# veter-cap.net
KiCad netlist of a schematic drawn in EAGLE
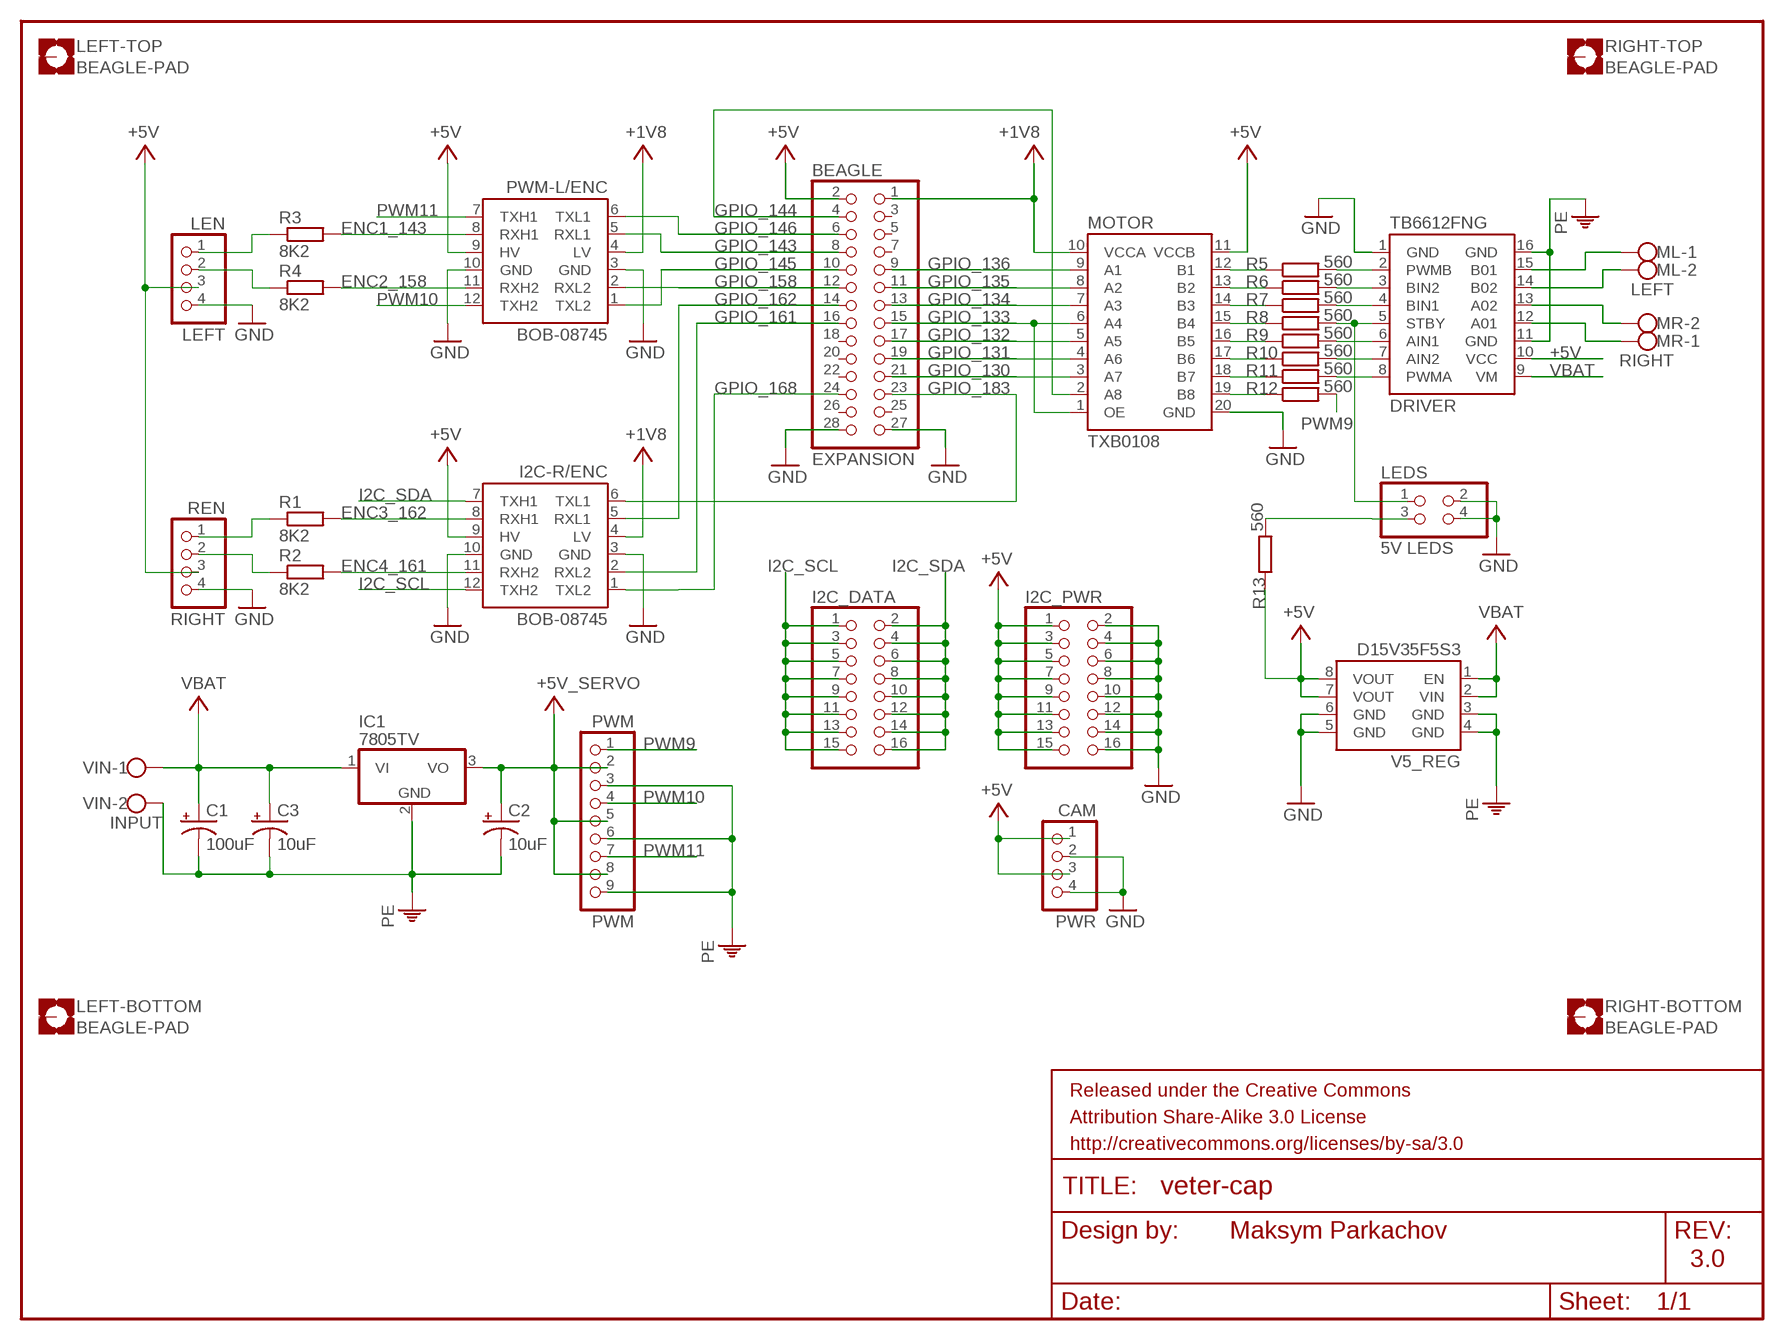
[diagram p0: schematic, sheet 1]

(export (version "E")
  (design (tool "Eeschema 10.0.6"))
  (components
    (comp (ref "BEAGLE")
      (value "EXPANSION")
      (footprint "eagle-import:BEAGLE_PINH2X14")
      (libsource (lib "eagle-import") (part "BEAGLE_EXPANSION"))
    )
    (comp (ref "C1")
      (value "100uF")
      (footprint "eagle-import:CPOL-RADIAL-10UF-25V")
      (libsource (lib "eagle-import") (part "CAP_POLPTH2"))
    )
    (comp (ref "C2")
      (value "10uF")
      (footprint "eagle-import:CPOL-RADIAL-10UF-25V")
      (libsource (lib "eagle-import") (part "CAP_POLPTH2"))
    )
    (comp (ref "C3")
      (value "10uF")
      (footprint "eagle-import:CPOL-RADIAL-10UF-25V")
      (libsource (lib "eagle-import") (part "CAP_POLPTH2"))
    )
    (comp (ref "CAM")
      (value "PWR")
      (footprint "eagle-import:1X04_90")
      (libsource (lib "eagle-import") (part "PINHD-1X4/90"))
    )
    (comp (ref "DRIVER")
      (value "TB6612FNG")
      (footprint "eagle-import:6612-BREAKOUT")
      (libsource (lib "eagle-import") (part "TB6612FNG"))
    )
    (comp (ref "FRAME1")
      (value "FRAME-LETTER")
      (footprint "eagle-import:CREATIVE_COMMONS")
      (libsource (lib "eagle-import") (part "FRAME-LETTER"))
    )
    (comp (ref "I2C-R/ENC")
      (value "BOB-08745")
      (footprint "eagle-import:BOB-08745-BREAKOUT")
      (libsource (lib "eagle-import") (part "BOB-08745"))
    )
    (comp (ref "I2C_DATA")
      (value "PINHD-2X8")
      (footprint "eagle-import:2X08")
      (libsource (lib "eagle-import") (part "PINHD-2X8"))
    )
    (comp (ref "I2C_PWR")
      (value "PINHD-2X8")
      (footprint "eagle-import:2X08")
      (libsource (lib "eagle-import") (part "PINHD-2X8"))
    )
    (comp (ref "IC1")
      (value "7805TV")
      (footprint "eagle-import:TO220V")
      (libsource (lib "eagle-import") (part "78TV05"))
    )
    (comp (ref "LEDS")
      (value "5V LEDS")
      (footprint "eagle-import:2X02")
      (libsource (lib "eagle-import") (part "PINHD-2X2"))
    )
    (comp (ref "LEFT-BOTTOM")
      (value "BEAGLE-PAD")
      (footprint "eagle-import:BEAGLE-PAD")
      (libsource (lib "eagle-import") (part "BEAGLE-PAD"))
    )
    (comp (ref "LEFT-TOP")
      (value "BEAGLE-PAD")
      (footprint "eagle-import:BEAGLE-PAD")
      (libsource (lib "eagle-import") (part "BEAGLE-PAD"))
    )
    (comp (ref "LEN")
      (value "LEFT")
      (footprint "eagle-import:1X04_90")
      (libsource (lib "eagle-import") (part "PINHD-1X4/90"))
    )
    (comp (ref "ML")
      (value "LEFT")
      (footprint "eagle-import:W237-102")
      (fields (field (name "MPN") "237-102"))
      (libsource (lib "eagle-import") (part "W237-102"))
    )
    (comp (ref "MOTOR")
      (value "TXB0108")
      (footprint "eagle-import:TXB0108-BREAKOUT")
      (libsource (lib "eagle-import") (part "TXB0108"))
    )
    (comp (ref "MR")
      (value "RIGHT")
      (footprint "eagle-import:W237-102")
      (fields (field (name "MPN") "237-102"))
      (libsource (lib "eagle-import") (part "W237-102"))
    )
    (comp (ref "PWM")
      (value "PWM")
      (footprint "eagle-import:1X09_90")
      (libsource (lib "eagle-import") (part "PINHD-1X9/90"))
    )
    (comp (ref "PWM-L/ENC")
      (value "BOB-08745")
      (footprint "eagle-import:BOB-08745-BREAKOUT")
      (libsource (lib "eagle-import") (part "BOB-08745"))
    )
    (comp (ref "R1")
      (value "8K2")
      (footprint "eagle-import:0207_10")
      (libsource (lib "eagle-import") (part "R-EU_0207/10"))
    )
    (comp (ref "R2")
      (value "8K2")
      (footprint "eagle-import:0207_10")
      (libsource (lib "eagle-import") (part "R-EU_0207/10"))
    )
    (comp (ref "R3")
      (value "8K2")
      (footprint "eagle-import:0207_10")
      (libsource (lib "eagle-import") (part "R-EU_0207/10"))
    )
    (comp (ref "R4")
      (value "8K2")
      (footprint "eagle-import:0207_10")
      (libsource (lib "eagle-import") (part "R-EU_0207/10"))
    )
    (comp (ref "R5")
      (value "560")
      (footprint "eagle-import:0207_10")
      (libsource (lib "eagle-import") (part "R-EU_0207/10"))
    )
    (comp (ref "R6")
      (value "560")
      (footprint "eagle-import:0207_10")
      (libsource (lib "eagle-import") (part "R-EU_0207/10"))
    )
    (comp (ref "R7")
      (value "560")
      (footprint "eagle-import:0207_10")
      (libsource (lib "eagle-import") (part "R-EU_0207/10"))
    )
    (comp (ref "R8")
      (value "560")
      (footprint "eagle-import:0207_10")
      (libsource (lib "eagle-import") (part "R-EU_0207/10"))
    )
    (comp (ref "R9")
      (value "560")
      (footprint "eagle-import:0207_10")
      (libsource (lib "eagle-import") (part "R-EU_0207/10"))
    )
    (comp (ref "R10")
      (value "560")
      (footprint "eagle-import:0207_10")
      (libsource (lib "eagle-import") (part "R-EU_0207/10"))
    )
    (comp (ref "R11")
      (value "560")
      (footprint "eagle-import:0207_10")
      (libsource (lib "eagle-import") (part "R-EU_0207/10"))
    )
    (comp (ref "R12")
      (value "560")
      (footprint "eagle-import:0207_10")
      (libsource (lib "eagle-import") (part "R-EU_0207/10"))
    )
    (comp (ref "R13")
      (value "560")
      (footprint "eagle-import:0207_10")
      (libsource (lib "eagle-import") (part "R-EU_0207/10"))
    )
    (comp (ref "REN")
      (value "RIGHT")
      (footprint "eagle-import:1X04_90")
      (libsource (lib "eagle-import") (part "PINHD-1X4/90"))
    )
    (comp (ref "RIGHT-BOTTOM")
      (value "BEAGLE-PAD")
      (footprint "eagle-import:BEAGLE-PAD")
      (libsource (lib "eagle-import") (part "BEAGLE-PAD"))
    )
    (comp (ref "RIGHT-TOP")
      (value "BEAGLE-PAD")
      (footprint "eagle-import:BEAGLE-PAD")
      (libsource (lib "eagle-import") (part "BEAGLE-PAD"))
    )
    (comp (ref "V5_REG")
      (value "D15V35F5S3")
      (footprint "eagle-import:D15V35F5S3-BREAKOUT")
      (libsource (lib "eagle-import") (part "D15V35F5S3"))
    )
    (comp (ref "VIN")
      (value "INPUT")
      (footprint "eagle-import:W237-102")
      (fields (field (name "MPN") "237-102"))
      (libsource (lib "eagle-import") (part "W237-102"))
    )
  )
  (nets
    (net (code "1") (name "+1V8") (class "Default")
      (node (ref "BEAGLE") (pin "1") (pinfunction "1_1") (pintype "passive"))
      (node (ref "I2C-R/ENC") (pin "4") (pinfunction "LV_4") (pintype "power_in"))
      (node (ref "MOTOR") (pin "10") (pinfunction "VCCA_10") (pintype "power_in"))
      (node (ref "PWM-L/ENC") (pin "4") (pinfunction "LV_4") (pintype "power_in"))
    )
    (net (code "2") (name "+5V") (class "Default")
      (node (ref "BEAGLE") (pin "2") (pinfunction "2_2") (pintype "passive"))
      (node (ref "CAM") (pin "1") (pinfunction "1_1") (pintype "passive"))
      (node (ref "CAM") (pin "3") (pinfunction "3_3") (pintype "passive"))
      (node (ref "DRIVER") (pin "10") (pinfunction "VCC_10") (pintype "power_in"))
      (node (ref "I2C-R/ENC") (pin "9") (pinfunction "HV_9") (pintype "power_in"))
      (node (ref "I2C_PWR") (pin "1") (pinfunction "1_1") (pintype "passive"))
      (node (ref "I2C_PWR") (pin "11") (pinfunction "11_11") (pintype "passive"))
      (node (ref "I2C_PWR") (pin "13") (pinfunction "13_13") (pintype "passive"))
      (node (ref "I2C_PWR") (pin "15") (pinfunction "15_15") (pintype "passive"))
      (node (ref "I2C_PWR") (pin "3") (pinfunction "3_3") (pintype "passive"))
      (node (ref "I2C_PWR") (pin "5") (pinfunction "5_5") (pintype "passive"))
      (node (ref "I2C_PWR") (pin "7") (pinfunction "7_7") (pintype "passive"))
      (node (ref "I2C_PWR") (pin "9") (pinfunction "9_9") (pintype "passive"))
      (node (ref "LEN") (pin "3") (pinfunction "3_3") (pintype "passive"))
      (node (ref "MOTOR") (pin "11") (pinfunction "VCCB_11") (pintype "power_in"))
      (node (ref "PWM-L/ENC") (pin "9") (pinfunction "HV_9") (pintype "power_in"))
      (node (ref "R13") (pin "1") (pinfunction "1_1") (pintype "passive"))
      (node (ref "REN") (pin "3") (pinfunction "3_3") (pintype "passive"))
      (node (ref "V5_REG") (pin "7") (pinfunction "VOUT_7") (pintype "power_in"))
      (node (ref "V5_REG") (pin "8") (pinfunction "VOUT_8") (pintype "power_in"))
    )
    (net (code "3") (name "+5V_SERVO") (class "Default")
      (node (ref "C2") (pin "1") (pinfunction "+_1") (pintype "passive"))
      (node (ref "IC1") (pin "3") (pinfunction "VO_3") (pintype "passive"))
      (node (ref "PWM") (pin "2") (pinfunction "2_2") (pintype "passive"))
      (node (ref "PWM") (pin "5") (pinfunction "5_5") (pintype "passive"))
      (node (ref "PWM") (pin "8") (pinfunction "8_8") (pintype "passive"))
    )
    (net (code "4") (name "/ENC1_143") (class "Default")
      (node (ref "PWM-L/ENC") (pin "8") (pinfunction "RXH1_8") (pintype "input"))
      (node (ref "R3") (pin "2") (pinfunction "2_2") (pintype "passive"))
    )
    (net (code "5") (name "/ENC2_158") (class "Default")
      (node (ref "PWM-L/ENC") (pin "11") (pinfunction "RXH2_11") (pintype "input"))
      (node (ref "R4") (pin "2") (pinfunction "2_2") (pintype "passive"))
    )
    (net (code "6") (name "/ENC3_162") (class "Default")
      (node (ref "I2C-R/ENC") (pin "8") (pinfunction "RXH1_8") (pintype "input"))
      (node (ref "R1") (pin "2") (pinfunction "2_2") (pintype "passive"))
    )
    (net (code "7") (name "/ENC4_161") (class "Default")
      (node (ref "I2C-R/ENC") (pin "11") (pinfunction "RXH2_11") (pintype "input"))
      (node (ref "R2") (pin "2") (pinfunction "2_2") (pintype "passive"))
    )
    (net (code "8") (name "/GPIO_130") (class "Default")
      (node (ref "BEAGLE") (pin "21") (pinfunction "21_21") (pintype "passive"))
      (node (ref "MOTOR") (pin "3") (pinfunction "A7_3") (pintype "input"))
    )
    (net (code "9") (name "/GPIO_131") (class "Default")
      (node (ref "BEAGLE") (pin "19") (pinfunction "19_19") (pintype "passive"))
      (node (ref "MOTOR") (pin "4") (pinfunction "A6_4") (pintype "input"))
    )
    (net (code "10") (name "/GPIO_132") (class "Default")
      (node (ref "BEAGLE") (pin "17") (pinfunction "17_17") (pintype "passive"))
      (node (ref "MOTOR") (pin "5") (pinfunction "A5_5") (pintype "input"))
    )
    (net (code "11") (name "/GPIO_133") (class "Default")
      (node (ref "BEAGLE") (pin "15") (pinfunction "15_15") (pintype "passive"))
      (node (ref "MOTOR") (pin "1") (pinfunction "OE_1") (pintype "input"))
      (node (ref "MOTOR") (pin "6") (pinfunction "A4_6") (pintype "input"))
    )
    (net (code "12") (name "/GPIO_134") (class "Default")
      (node (ref "BEAGLE") (pin "13") (pinfunction "13_13") (pintype "passive"))
      (node (ref "MOTOR") (pin "7") (pinfunction "A3_7") (pintype "input"))
    )
    (net (code "13") (name "/GPIO_135") (class "Default")
      (node (ref "BEAGLE") (pin "11") (pinfunction "11_11") (pintype "passive"))
      (node (ref "MOTOR") (pin "8") (pinfunction "A2_8") (pintype "bidirectional"))
    )
    (net (code "14") (name "/GPIO_136") (class "Default")
      (node (ref "BEAGLE") (pin "9") (pinfunction "9_9") (pintype "passive"))
      (node (ref "MOTOR") (pin "9") (pinfunction "A1_9") (pintype "input"))
    )
    (net (code "15") (name "/GPIO_143") (class "Default")
      (node (ref "BEAGLE") (pin "8") (pinfunction "8_8") (pintype "passive"))
      (node (ref "PWM-L/ENC") (pin "5") (pinfunction "RXL1_5") (pintype "output"))
    )
    (net (code "16") (name "/GPIO_144") (class "Default")
      (node (ref "BEAGLE") (pin "4") (pinfunction "4_4") (pintype "passive"))
      (node (ref "MOTOR") (pin "2") (pinfunction "A8_2") (pintype "input"))
    )
    (net (code "17") (name "/GPIO_145") (class "Default")
      (node (ref "BEAGLE") (pin "10") (pinfunction "10_10") (pintype "passive"))
      (node (ref "PWM-L/ENC") (pin "1") (pinfunction "TXL2_1") (pintype "input"))
    )
    (net (code "18") (name "/GPIO_146") (class "Default")
      (node (ref "BEAGLE") (pin "6") (pinfunction "6_6") (pintype "passive"))
      (node (ref "PWM-L/ENC") (pin "6") (pinfunction "TXL1_6") (pintype "input"))
    )
    (net (code "19") (name "/GPIO_158") (class "Default")
      (node (ref "BEAGLE") (pin "12") (pinfunction "12_12") (pintype "passive"))
      (node (ref "PWM-L/ENC") (pin "2") (pinfunction "RXL2_2") (pintype "output"))
    )
    (net (code "20") (name "/GPIO_161") (class "Default")
      (node (ref "BEAGLE") (pin "16") (pinfunction "16_16") (pintype "passive"))
      (node (ref "I2C-R/ENC") (pin "2") (pinfunction "RXL2_2") (pintype "output"))
    )
    (net (code "21") (name "/GPIO_162") (class "Default")
      (node (ref "BEAGLE") (pin "14") (pinfunction "14_14") (pintype "passive"))
      (node (ref "I2C-R/ENC") (pin "5") (pinfunction "RXL1_5") (pintype "output"))
    )
    (net (code "22") (name "/GPIO_168") (class "Default")
      (node (ref "BEAGLE") (pin "24") (pinfunction "24_24") (pintype "passive"))
      (node (ref "I2C-R/ENC") (pin "1") (pinfunction "TXL2_1") (pintype "input"))
    )
    (net (code "23") (name "/GPIO_183") (class "Default")
      (node (ref "BEAGLE") (pin "23") (pinfunction "23_23") (pintype "passive"))
      (node (ref "I2C-R/ENC") (pin "6") (pinfunction "TXL1_6") (pintype "input"))
    )
    (net (code "24") (name "/I2C_SCL") (class "Default")
      (node (ref "I2C-R/ENC") (pin "12") (pinfunction "TXH2_12") (pintype "output"))
      (node (ref "I2C_DATA") (pin "1") (pinfunction "1_1") (pintype "passive"))
      (node (ref "I2C_DATA") (pin "11") (pinfunction "11_11") (pintype "passive"))
      (node (ref "I2C_DATA") (pin "13") (pinfunction "13_13") (pintype "passive"))
      (node (ref "I2C_DATA") (pin "15") (pinfunction "15_15") (pintype "passive"))
      (node (ref "I2C_DATA") (pin "3") (pinfunction "3_3") (pintype "passive"))
      (node (ref "I2C_DATA") (pin "5") (pinfunction "5_5") (pintype "passive"))
      (node (ref "I2C_DATA") (pin "7") (pinfunction "7_7") (pintype "passive"))
      (node (ref "I2C_DATA") (pin "9") (pinfunction "9_9") (pintype "passive"))
    )
    (net (code "25") (name "/I2C_SDA") (class "Default")
      (node (ref "I2C-R/ENC") (pin "7") (pinfunction "TXH1_7") (pintype "output"))
      (node (ref "I2C_DATA") (pin "10") (pinfunction "10_10") (pintype "passive"))
      (node (ref "I2C_DATA") (pin "12") (pinfunction "12_12") (pintype "passive"))
      (node (ref "I2C_DATA") (pin "14") (pinfunction "14_14") (pintype "passive"))
      (node (ref "I2C_DATA") (pin "16") (pinfunction "16_16") (pintype "passive"))
      (node (ref "I2C_DATA") (pin "2") (pinfunction "2_2") (pintype "passive"))
      (node (ref "I2C_DATA") (pin "4") (pinfunction "4_4") (pintype "passive"))
      (node (ref "I2C_DATA") (pin "6") (pinfunction "6_6") (pintype "passive"))
      (node (ref "I2C_DATA") (pin "8") (pinfunction "8_8") (pintype "passive"))
    )
    (net (code "26") (name "/PWM9") (class "Default")
      (node (ref "PWM") (pin "1") (pinfunction "1_1") (pintype "passive"))
      (node (ref "R12") (pin "2") (pinfunction "2_2") (pintype "passive"))
    )
    (net (code "27") (name "/PWM10") (class "Default")
      (node (ref "PWM") (pin "4") (pinfunction "4_4") (pintype "passive"))
      (node (ref "PWM-L/ENC") (pin "12") (pinfunction "TXH2_12") (pintype "output"))
    )
    (net (code "28") (name "/PWM11") (class "Default")
      (node (ref "PWM") (pin "7") (pinfunction "7_7") (pintype "passive"))
      (node (ref "PWM-L/ENC") (pin "7") (pinfunction "TXH1_7") (pintype "output"))
    )
    (net (code "29") (name "GND") (class "Default")
      (node (ref "BEAGLE") (pin "27") (pinfunction "27_27") (pintype "passive"))
      (node (ref "BEAGLE") (pin "28") (pinfunction "28_28") (pintype "passive"))
      (node (ref "CAM") (pin "2") (pinfunction "2_2") (pintype "passive"))
      (node (ref "CAM") (pin "4") (pinfunction "4_4") (pintype "passive"))
      (node (ref "DRIVER") (pin "1") (pinfunction "GND_1") (pintype "power_in"))
      (node (ref "I2C-R/ENC") (pin "10") (pinfunction "GND_10") (pintype "power_in"))
      (node (ref "I2C-R/ENC") (pin "3") (pinfunction "GND_3") (pintype "power_in"))
      (node (ref "I2C_PWR") (pin "10") (pinfunction "10_10") (pintype "passive"))
      (node (ref "I2C_PWR") (pin "12") (pinfunction "12_12") (pintype "passive"))
      (node (ref "I2C_PWR") (pin "14") (pinfunction "14_14") (pintype "passive"))
      (node (ref "I2C_PWR") (pin "16") (pinfunction "16_16") (pintype "passive"))
      (node (ref "I2C_PWR") (pin "2") (pinfunction "2_2") (pintype "passive"))
      (node (ref "I2C_PWR") (pin "4") (pinfunction "4_4") (pintype "passive"))
      (node (ref "I2C_PWR") (pin "6") (pinfunction "6_6") (pintype "passive"))
      (node (ref "I2C_PWR") (pin "8") (pinfunction "8_8") (pintype "passive"))
      (node (ref "LEDS") (pin "2") (pinfunction "2_2") (pintype "passive"))
      (node (ref "LEDS") (pin "4") (pinfunction "4_4") (pintype "passive"))
      (node (ref "LEN") (pin "4") (pinfunction "4_4") (pintype "passive"))
      (node (ref "MOTOR") (pin "20") (pinfunction "GND_20") (pintype "power_in"))
      (node (ref "PWM-L/ENC") (pin "10") (pinfunction "GND_10") (pintype "power_in"))
      (node (ref "PWM-L/ENC") (pin "3") (pinfunction "GND_3") (pintype "power_in"))
      (node (ref "REN") (pin "4") (pinfunction "4_4") (pintype "passive"))
      (node (ref "V5_REG") (pin "5") (pinfunction "GND_5") (pintype "power_in"))
      (node (ref "V5_REG") (pin "6") (pinfunction "GND_6") (pintype "power_in"))
    )
    (net (code "30") (name "Net-(DRIVER-A01)") (class "Default")
      (node (ref "DRIVER") (pin "12") (pinfunction "A01_12") (pintype "output"))
      (node (ref "MR") (pin "1") (pinfunction "KL_1") (pintype "passive"))
    )
    (net (code "31") (name "Net-(DRIVER-A02)") (class "Default")
      (node (ref "DRIVER") (pin "13") (pinfunction "A02_13") (pintype "output"))
      (node (ref "MR") (pin "2") (pinfunction "KL_2") (pintype "passive"))
    )
    (net (code "32") (name "Net-(DRIVER-AIN1)") (class "Default")
      (node (ref "DRIVER") (pin "6") (pinfunction "AIN1_6") (pintype "bidirectional"))
      (node (ref "R9") (pin "2") (pinfunction "2_2") (pintype "passive"))
    )
    (net (code "33") (name "Net-(DRIVER-AIN2)") (class "Default")
      (node (ref "DRIVER") (pin "7") (pinfunction "AIN2_7") (pintype "input"))
      (node (ref "R10") (pin "2") (pinfunction "2_2") (pintype "passive"))
    )
    (net (code "34") (name "Net-(DRIVER-B01)") (class "Default")
      (node (ref "DRIVER") (pin "15") (pinfunction "B01_15") (pintype "output"))
      (node (ref "ML") (pin "1") (pinfunction "KL_1") (pintype "passive"))
    )
    (net (code "35") (name "Net-(DRIVER-B02)") (class "Default")
      (node (ref "DRIVER") (pin "14") (pinfunction "B02_14") (pintype "output"))
      (node (ref "ML") (pin "2") (pinfunction "KL_2") (pintype "passive"))
    )
    (net (code "36") (name "Net-(DRIVER-BIN1)") (class "Default")
      (node (ref "DRIVER") (pin "4") (pinfunction "BIN1_4") (pintype "input"))
      (node (ref "R7") (pin "2") (pinfunction "2_2") (pintype "passive"))
    )
    (net (code "37") (name "Net-(DRIVER-BIN2)") (class "Default")
      (node (ref "DRIVER") (pin "3") (pinfunction "BIN2_3") (pintype "input"))
      (node (ref "R6") (pin "2") (pinfunction "2_2") (pintype "passive"))
    )
    (net (code "38") (name "Net-(DRIVER-PWMA)") (class "Default")
      (node (ref "DRIVER") (pin "8") (pinfunction "PWMA_8") (pintype "input"))
      (node (ref "R11") (pin "2") (pinfunction "2_2") (pintype "passive"))
    )
    (net (code "39") (name "Net-(DRIVER-PWMB)") (class "Default")
      (node (ref "DRIVER") (pin "2") (pinfunction "PWMB_2") (pintype "input"))
      (node (ref "R5") (pin "2") (pinfunction "2_2") (pintype "passive"))
    )
    (net (code "40") (name "Net-(DRIVER-STBY)") (class "Default")
      (node (ref "DRIVER") (pin "5") (pinfunction "STBY_5") (pintype "input"))
      (node (ref "LEDS") (pin "1") (pinfunction "1_1") (pintype "passive"))
      (node (ref "R8") (pin "2") (pinfunction "2_2") (pintype "passive"))
    )
    (net (code "41") (name "Net-(LEDS-Pad3)") (class "Default")
      (node (ref "LEDS") (pin "3") (pinfunction "3_3") (pintype "passive"))
      (node (ref "R13") (pin "2") (pinfunction "2_2") (pintype "passive"))
    )
    (net (code "42") (name "Net-(LEN-Pad1)") (class "Default")
      (node (ref "LEN") (pin "1") (pinfunction "1_1") (pintype "passive"))
      (node (ref "R3") (pin "1") (pinfunction "1_1") (pintype "passive"))
    )
    (net (code "43") (name "Net-(LEN-Pad2)") (class "Default")
      (node (ref "LEN") (pin "2") (pinfunction "2_2") (pintype "passive"))
      (node (ref "R4") (pin "1") (pinfunction "1_1") (pintype "passive"))
    )
    (net (code "44") (name "Net-(MOTOR-B1)") (class "Default")
      (node (ref "MOTOR") (pin "12") (pinfunction "B1_12") (pintype "output"))
      (node (ref "R5") (pin "1") (pinfunction "1_1") (pintype "passive"))
    )
    (net (code "45") (name "Net-(MOTOR-B2)") (class "Default")
      (node (ref "MOTOR") (pin "13") (pinfunction "B2_13") (pintype "output"))
      (node (ref "R6") (pin "1") (pinfunction "1_1") (pintype "passive"))
    )
    (net (code "46") (name "Net-(MOTOR-B3)") (class "Default")
      (node (ref "MOTOR") (pin "14") (pinfunction "B3_14") (pintype "output"))
      (node (ref "R7") (pin "1") (pinfunction "1_1") (pintype "passive"))
    )
    (net (code "47") (name "Net-(MOTOR-B4)") (class "Default")
      (node (ref "MOTOR") (pin "15") (pinfunction "B4_15") (pintype "output"))
      (node (ref "R8") (pin "1") (pinfunction "1_1") (pintype "passive"))
    )
    (net (code "48") (name "Net-(MOTOR-B5)") (class "Default")
      (node (ref "MOTOR") (pin "16") (pinfunction "B5_16") (pintype "output"))
      (node (ref "R9") (pin "1") (pinfunction "1_1") (pintype "passive"))
    )
    (net (code "49") (name "Net-(MOTOR-B6)") (class "Default")
      (node (ref "MOTOR") (pin "17") (pinfunction "B6_17") (pintype "output"))
      (node (ref "R10") (pin "1") (pinfunction "1_1") (pintype "passive"))
    )
    (net (code "50") (name "Net-(MOTOR-B7)") (class "Default")
      (node (ref "MOTOR") (pin "18") (pinfunction "B7_18") (pintype "output"))
      (node (ref "R11") (pin "1") (pinfunction "1_1") (pintype "passive"))
    )
    (net (code "51") (name "Net-(MOTOR-B8)") (class "Default")
      (node (ref "MOTOR") (pin "19") (pinfunction "B8_19") (pintype "output"))
      (node (ref "R12") (pin "1") (pinfunction "1_1") (pintype "passive"))
    )
    (net (code "52") (name "Net-(R1-Pad1)") (class "Default")
      (node (ref "R1") (pin "1") (pinfunction "1_1") (pintype "passive"))
      (node (ref "REN") (pin "1") (pinfunction "1_1") (pintype "passive"))
    )
    (net (code "53") (name "Net-(R2-Pad1)") (class "Default")
      (node (ref "R2") (pin "1") (pinfunction "1_1") (pintype "passive"))
      (node (ref "REN") (pin "2") (pinfunction "2_2") (pintype "passive"))
    )
    (net (code "54") (name "PE") (class "Default")
      (node (ref "C1") (pin "2") (pinfunction "-_2") (pintype "passive"))
      (node (ref "C2") (pin "2") (pinfunction "-_2") (pintype "passive"))
      (node (ref "C3") (pin "2") (pinfunction "-_2") (pintype "passive"))
      (node (ref "DRIVER") (pin "11") (pinfunction "GND_11") (pintype "power_in"))
      (node (ref "DRIVER") (pin "16") (pinfunction "GND_16") (pintype "power_in"))
      (node (ref "IC1") (pin "2") (pinfunction "GND_2") (pintype "passive"))
      (node (ref "PWM") (pin "3") (pinfunction "3_3") (pintype "passive"))
      (node (ref "PWM") (pin "6") (pinfunction "6_6") (pintype "passive"))
      (node (ref "PWM") (pin "9") (pinfunction "9_9") (pintype "passive"))
      (node (ref "V5_REG") (pin "3") (pinfunction "GND_3") (pintype "power_in"))
      (node (ref "V5_REG") (pin "4") (pinfunction "GND_4") (pintype "power_in"))
      (node (ref "VIN") (pin "2") (pinfunction "KL_2") (pintype "passive"))
    )
    (net (code "55") (name "VBAT") (class "Default")
      (node (ref "C1") (pin "1") (pinfunction "+_1") (pintype "passive"))
      (node (ref "C3") (pin "1") (pinfunction "+_1") (pintype "passive"))
      (node (ref "DRIVER") (pin "9") (pinfunction "VM_9") (pintype "power_in"))
      (node (ref "IC1") (pin "1") (pinfunction "VI_1") (pintype "input"))
      (node (ref "V5_REG") (pin "1") (pinfunction "EN_1") (pintype "input"))
      (node (ref "V5_REG") (pin "2") (pinfunction "VIN_2") (pintype "power_in"))
      (node (ref "VIN") (pin "1") (pinfunction "KL_1") (pintype "passive"))
    )
    (net (code "56") (name "unconnected-(BEAGLE-Pad3)") (class "Default")
      (node (ref "BEAGLE") (pin "3") (pinfunction "3_3") (pintype "passive"))
    )
    (net (code "57") (name "unconnected-(BEAGLE-Pad5)") (class "Default")
      (node (ref "BEAGLE") (pin "5") (pinfunction "5_5") (pintype "passive"))
    )
    (net (code "58") (name "unconnected-(BEAGLE-Pad7)") (class "Default")
      (node (ref "BEAGLE") (pin "7") (pinfunction "7_7") (pintype "passive"))
    )
    (net (code "59") (name "unconnected-(BEAGLE-Pad18)") (class "Default")
      (node (ref "BEAGLE") (pin "18") (pinfunction "18_18") (pintype "passive"))
    )
    (net (code "60") (name "unconnected-(BEAGLE-Pad20)") (class "Default")
      (node (ref "BEAGLE") (pin "20") (pinfunction "20_20") (pintype "passive"))
    )
    (net (code "61") (name "unconnected-(BEAGLE-Pad22)") (class "Default")
      (node (ref "BEAGLE") (pin "22") (pinfunction "22_22") (pintype "passive"))
    )
    (net (code "62") (name "unconnected-(BEAGLE-Pad25)") (class "Default")
      (node (ref "BEAGLE") (pin "25") (pinfunction "25_25") (pintype "passive"))
    )
    (net (code "63") (name "unconnected-(BEAGLE-Pad26)") (class "Default")
      (node (ref "BEAGLE") (pin "26") (pinfunction "26_26") (pintype "passive"))
    )
    (net (code "64") (name "unconnected-(LEFT-BOTTOM-MOUNT-PadB4,1)") (class "Default")
      (node (ref "LEFT-BOTTOM") (pin "B4,1") (pinfunction "MOUNT_B4,1") (pintype "passive"))
    )
    (net (code "65") (name "unconnected-(LEFT-TOP-MOUNT-PadB4,1)") (class "Default")
      (node (ref "LEFT-TOP") (pin "B4,1") (pinfunction "MOUNT_B4,1") (pintype "passive"))
    )
    (net (code "66") (name "unconnected-(RIGHT-BOTTOM-MOUNT-PadB4,1)") (class "Default")
      (node (ref "RIGHT-BOTTOM") (pin "B4,1") (pinfunction "MOUNT_B4,1") (pintype "passive"))
    )
    (net (code "67") (name "unconnected-(RIGHT-TOP-MOUNT-PadB4,1)") (class "Default")
      (node (ref "RIGHT-TOP") (pin "B4,1") (pinfunction "MOUNT_B4,1") (pintype "passive"))
    )
  )
)
